# PIC32MZ_cam_sch.net
KiCad netlist of a schematic drawn in Altium Designer
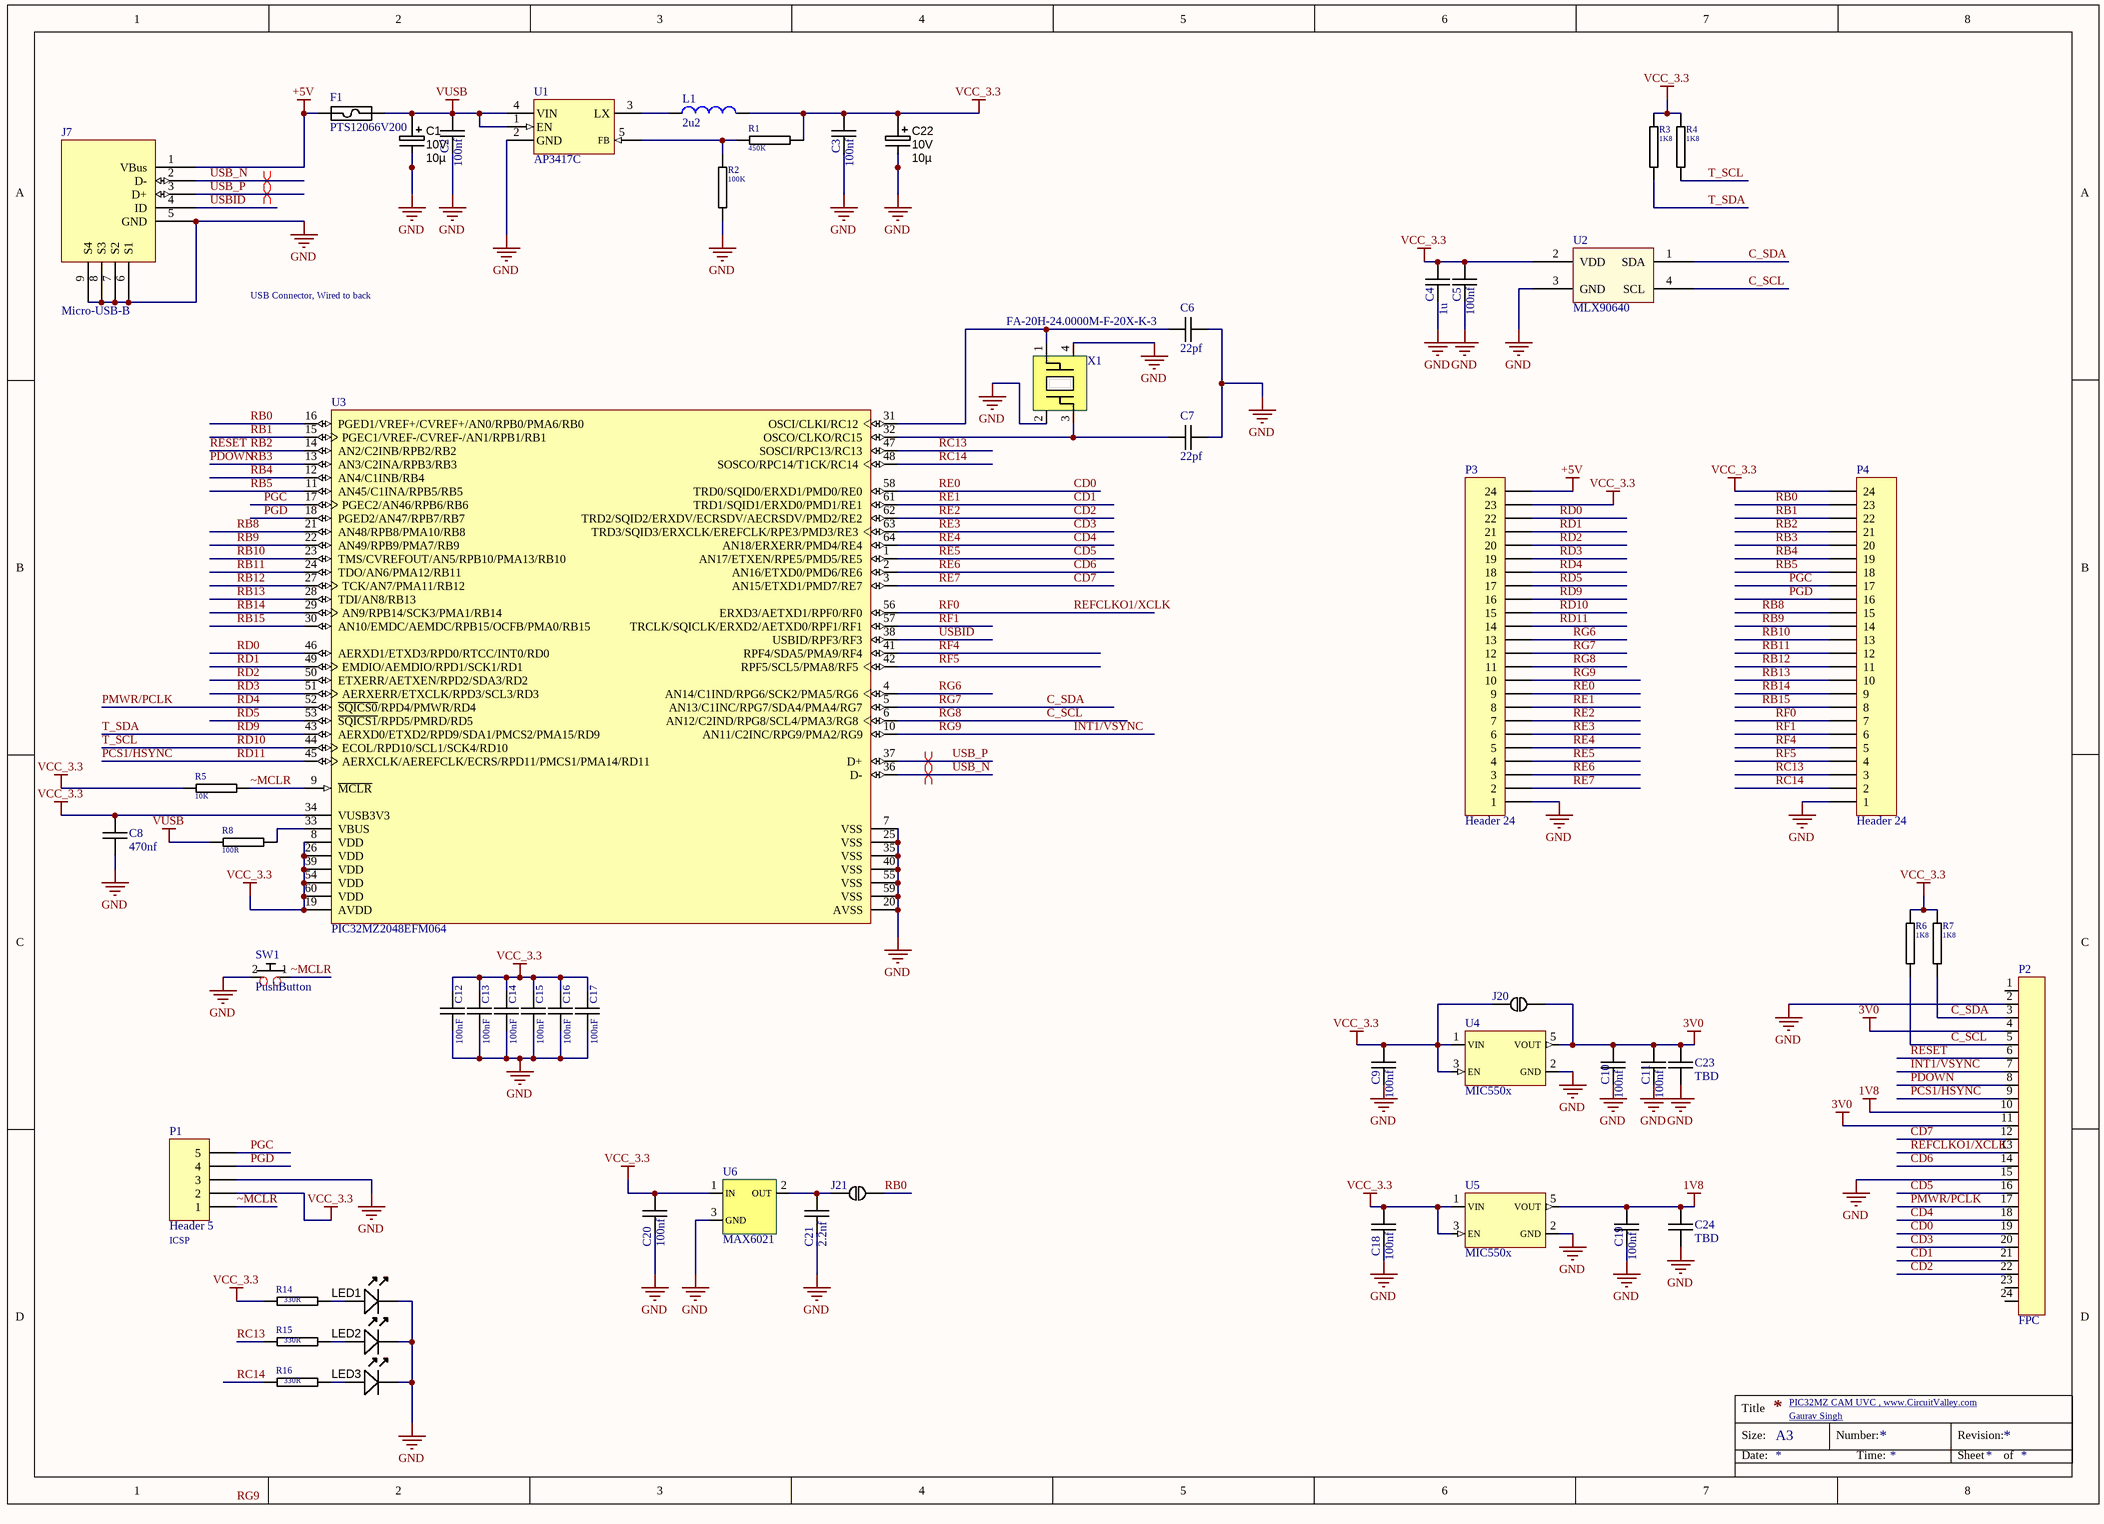
[diagram p0: PIC32MZ_cam_sch.SchDoc]

(export (version "E")
  (design (tool "Eeschema 10.0.6"))
  (components
    (comp (ref "C1")
      (value "10µ")
      (footprint "CAPMP3528X210N")
      (description "Capacitor SMD Tantalum 47uF 20% 6.3V 1210")
      (fields (field (name "TOLERANCE") "±20%") (field (name "RATINGS") "10V"))
      (libsource (lib "PBL - Capacitors") (part "CAPT_47u_1210_6V3"))
    )
    (comp (ref "C2")
      (value "100nf")
      (footprint "0603C-GENERIC")
      (description "CAPACITOR 0603 CERAMIC")
      (fields
        (field (name "MANUFACTURER") "Murata Electronics North America")
        (field (name "MANUFACTURER PART NUMBER") "GRM188R60J106ME47D")
      )
      (libsource (lib "Generic") (part "0603C-10UF-6V3-X5R-MUR"))
    )
    (comp (ref "C3")
      (value "100nf")
      (footprint "0603C-GENERIC")
      (description "CAPACITOR 0603 CERAMIC")
      (fields
        (field (name "MANUFACTURER") "Murata Electronics North America")
        (field (name "MANUFACTURER PART NUMBER") "GRM188R60J106ME47D")
      )
      (libsource (lib "Generic") (part "0603C-10UF-6V3-X5R-MUR"))
    )
    (comp (ref "C4")
      (value "1u")
      (footprint "0603C-GENERIC")
      (description "CAPACITOR 0603 CERAMIC")
      (fields
        (field (name "MANUFACTURER") "Murata Electronics North America")
        (field (name "MANUFACTURER PART NUMBER") "GRM188R60J106ME47D")
      )
      (libsource (lib "Generic") (part "0603C-10UF-6V3-X5R-MUR"))
    )
    (comp (ref "C5")
      (value "100nf")
      (footprint "0603C-GENERIC")
      (description "CAPACITOR 0603 CERAMIC")
      (fields
        (field (name "MANUFACTURER") "Murata Electronics North America")
        (field (name "MANUFACTURER PART NUMBER") "GRM188R60J106ME47D")
      )
      (libsource (lib "Generic") (part "0603C-10UF-6V3-X5R-MUR"))
    )
    (comp (ref "C6")
      (value "22pf")
      (footprint "0603C-GENERIC")
      (description "CAPACITOR 0603 CERAMIC")
      (fields
        (field (name "MANUFACTURER") "Murata Electronics North America")
        (field (name "MANUFACTURER PART NUMBER") "GRM188R60J106ME47D")
      )
      (libsource (lib "Generic") (part "0603C-10UF-6V3-X5R-MUR"))
    )
    (comp (ref "C7")
      (value "22pf")
      (footprint "0603C-GENERIC")
      (description "CAPACITOR 0603 CERAMIC")
      (fields
        (field (name "MANUFACTURER") "Murata Electronics North America")
        (field (name "MANUFACTURER PART NUMBER") "GRM188R60J106ME47D")
      )
      (libsource (lib "Generic") (part "0603C-10UF-6V3-X5R-MUR"))
    )
    (comp (ref "C8")
      (value "470nf")
      (footprint "0603C-GENERIC")
      (description "CAPACITOR 0603 CERAMIC")
      (fields
        (field (name "MANUFACTURER") "Murata Electronics North America")
        (field (name "MANUFACTURER PART NUMBER") "GRM188R60J106ME47D")
      )
      (libsource (lib "Generic") (part "0603C-10UF-6V3-X5R-MUR"))
    )
    (comp (ref "C9")
      (value "100nf")
      (footprint "0603C-GENERIC")
      (description "CAPACITOR 0603 CERAMIC")
      (fields
        (field (name "MANUFACTURER") "Murata Electronics North America")
        (field (name "MANUFACTURER PART NUMBER") "GRM188R60J106ME47D")
      )
      (libsource (lib "Generic") (part "0603C-10UF-6V3-X5R-MUR"))
    )
    (comp (ref "C10")
      (value "100nf")
      (footprint "0603C-GENERIC")
      (description "CAPACITOR 0603 CERAMIC")
      (fields
        (field (name "MANUFACTURER") "Murata Electronics North America")
        (field (name "MANUFACTURER PART NUMBER") "GRM188R60J106ME47D")
      )
      (libsource (lib "Generic") (part "0603C-10UF-6V3-X5R-MUR"))
    )
    (comp (ref "C11")
      (value "100nf")
      (footprint "0603C-GENERIC")
      (description "CAPACITOR 0603 CERAMIC")
      (fields
        (field (name "MANUFACTURER") "Murata Electronics North America")
        (field (name "MANUFACTURER PART NUMBER") "GRM188R60J106ME47D")
      )
      (libsource (lib "Generic") (part "0603C-10UF-6V3-X5R-MUR"))
    )
    (comp (ref "C12")
      (value "100nF")
      (footprint "0603C-GENERIC")
      (description "CAPACITOR 0603 CERAMIC")
      (fields
        (field (name "MANUFACTURER PART NUMBER") "C1608X7R1E104K")
        (field (name "MANUFACTURER") "TDK Corporation")
      )
      (libsource (lib "Generic") (part "0603C-100NF-25V-X7R-TDK"))
    )
    (comp (ref "C13")
      (value "100nF")
      (footprint "0603C-GENERIC")
      (description "CAPACITOR 0603 CERAMIC")
      (fields
        (field (name "MANUFACTURER PART NUMBER") "C1608X7R1E104K")
        (field (name "MANUFACTURER") "TDK Corporation")
      )
      (libsource (lib "Generic") (part "0603C-100NF-25V-X7R-TDK"))
    )
    (comp (ref "C14")
      (value "100nF")
      (footprint "0603C-GENERIC")
      (description "CAPACITOR 0603 CERAMIC")
      (fields
        (field (name "MANUFACTURER PART NUMBER") "C1608X7R1E104K")
        (field (name "MANUFACTURER") "TDK Corporation")
      )
      (libsource (lib "Generic") (part "0603C-100NF-25V-X7R-TDK"))
    )
    (comp (ref "C15")
      (value "100nF")
      (footprint "0603C-GENERIC")
      (description "CAPACITOR 0603 CERAMIC")
      (fields
        (field (name "MANUFACTURER PART NUMBER") "C1608X7R1E104K")
        (field (name "MANUFACTURER") "TDK Corporation")
      )
      (libsource (lib "Generic") (part "0603C-100NF-25V-X7R-TDK"))
    )
    (comp (ref "C16")
      (value "100nF")
      (footprint "0603C-GENERIC")
      (description "CAPACITOR 0603 CERAMIC")
      (fields
        (field (name "MANUFACTURER PART NUMBER") "C1608X7R1E104K")
        (field (name "MANUFACTURER") "TDK Corporation")
      )
      (libsource (lib "Generic") (part "0603C-100NF-25V-X7R-TDK"))
    )
    (comp (ref "C17")
      (value "100nF")
      (footprint "0603C-GENERIC")
      (description "CAPACITOR 0603 CERAMIC")
      (fields
        (field (name "MANUFACTURER PART NUMBER") "C1608X7R1E104K")
        (field (name "MANUFACTURER") "TDK Corporation")
      )
      (libsource (lib "Generic") (part "0603C-100NF-25V-X7R-TDK"))
    )
    (comp (ref "C18")
      (value "100nf")
      (footprint "0603C-GENERIC")
      (description "CAPACITOR 0603 CERAMIC")
      (fields
        (field (name "MANUFACTURER") "Murata Electronics North America")
        (field (name "MANUFACTURER PART NUMBER") "GRM188R60J106ME47D")
      )
      (libsource (lib "Generic") (part "0603C-10UF-6V3-X5R-MUR"))
    )
    (comp (ref "C19")
      (value "100nf")
      (footprint "0603C-GENERIC")
      (description "CAPACITOR 0603 CERAMIC")
      (fields
        (field (name "MANUFACTURER") "Murata Electronics North America")
        (field (name "MANUFACTURER PART NUMBER") "GRM188R60J106ME47D")
      )
      (libsource (lib "Generic") (part "0603C-10UF-6V3-X5R-MUR"))
    )
    (comp (ref "C20")
      (value "100nf")
      (footprint "0603C-GENERIC")
      (description "CAPACITOR 0603 CERAMIC")
      (fields
        (field (name "MANUFACTURER") "Murata Electronics North America")
        (field (name "MANUFACTURER PART NUMBER") "GRM188R60J106ME47D")
      )
      (libsource (lib "Generic") (part "0603C-10UF-6V3-X5R-MUR"))
    )
    (comp (ref "C21")
      (value "2.2nf")
      (footprint "0603C-GENERIC")
      (description "CAPACITOR 0603 CERAMIC")
      (fields
        (field (name "MANUFACTURER") "Murata Electronics North America")
        (field (name "MANUFACTURER PART NUMBER") "GRM188R60J106ME47D")
      )
      (libsource (lib "Generic") (part "0603C-10UF-6V3-X5R-MUR"))
    )
    (comp (ref "C22")
      (value "10µ")
      (footprint "CAPMP3528X210N")
      (description "Capacitor SMD Tantalum 47uF 20% 6.3V 1210")
      (fields (field (name "TOLERANCE") "±20%") (field (name "RATINGS") "10V"))
      (libsource (lib "PBL - Capacitors") (part "CAPT_47u_1210_6V3"))
    )
    (comp (ref "C23")
      (value "TBD")
      (footprint "0805C-TBD")
      (description "CAPACITOR 0805 CERAMIC VALUE TO BE DETERMINED")
      (libsource (lib "Generic") (part "0805C-TBD"))
    )
    (comp (ref "C24")
      (value "TBD")
      (footprint "0805C-TBD")
      (description "CAPACITOR 0805 CERAMIC VALUE TO BE DETERMINED")
      (libsource (lib "Generic") (part "0805C-TBD"))
    )
    (comp (ref "F1")
      (value "PTS12066V200")
      (footprint "RESC3216N")
      (description "GENERIC FUSE")
      (libsource (lib "Generic") (part "FUSE-GENERIC"))
    )
    (comp (ref "J7")
      (value "Micro-USB-B")
      (footprint "10118193-0001lfc")
      (fields (field (name "PART") "10118193-0001lfc"))
      (libsource (lib "USB-MICROB-HW-MC-5F") (part "Micro-USB-B"))
    )
    (comp (ref "J20")
      (value "BYPASS-MINI")
      (footprint "BYPASS-MINI")
      (description "SOLDERDOT BYPASS")
      (libsource (lib "Generic") (part "BYPASS-MINI"))
    )
    (comp (ref "J21")
      (value "BYPASS-MINI")
      (footprint "BYPASS-MINI")
      (description "SOLDERDOT BYPASS")
      (libsource (lib "Generic") (part "BYPASS-MINI"))
    )
    (comp (ref "L1")
      (value "2u2")
      (footprint "TAIYO_NRS4018T2R2MDGJ")
      (fields (field (name "PARTNUMBER") "NRS4018T2R2MDGJ"))
      (libsource (lib "Inductor") (part "inductor_smd"))
    )
    (comp (ref "LED1")
      (value "Blue")
      (footprint "LED-0805-K")
      (description "LED 0805 SMD Blue 100mcd 470nm")
      (libsource (lib "PBL - Light Sources") (part "LED_SMD_Blue_0805_100mcd"))
    )
    (comp (ref "LED2")
      (value "Blue")
      (footprint "LED-0805-K")
      (description "LED 0805 SMD Blue 100mcd 470nm")
      (libsource (lib "PBL - Light Sources") (part "LED_SMD_Blue_0805_100mcd"))
    )
    (comp (ref "LED3")
      (value "Blue")
      (footprint "LED-0805-K")
      (description "LED 0805 SMD Blue 100mcd 470nm")
      (libsource (lib "PBL - Light Sources") (part "LED_SMD_Blue_0805_100mcd"))
    )
    (comp (ref "P1")
      (value "Header 5")
      (footprint "HDR1X5")
      (description "Header, 5-Pin")
      (fields (field (name "PUBLISHER") "Altium Limited"))
      (libsource (lib "Miscellaneous Connectors") (part "Header 5"))
    )
    (comp (ref "P2") (value "FPC") (footprint "OV7xxx Cam") (libsource (lib "cvlib") (part "FPC24_PIN")))
    (comp (ref "P3")
      (value "Header 24")
      (footprint "HDR1X24")
      (description "Header, 24-Pin")
      (fields (field (name "PUBLISHER") "Altium Limited"))
      (libsource (lib "Miscellaneous Connectors") (part "Header 24"))
    )
    (comp (ref "P4")
      (value "Header 24")
      (footprint "HDR1X24")
      (description "Header, 24-Pin")
      (fields (field (name "PUBLISHER") "Altium Limited"))
      (libsource (lib "") (part "Header 24_1"))
    )
    (comp (ref "R1")
      (value "450K")
      (footprint "0603R-10K")
      (description "GENERIC RESISTOR 0603")
      (fields (field (name "MANUFACTURER") "Stackpole Electronics Inc") (field (name "TOLERANCE") "±1%"))
      (libsource (lib "Generic") (part "0603R-10K"))
    )
    (comp (ref "R2")
      (value "100K")
      (footprint "0603R-10K")
      (description "GENERIC RESISTOR 0603")
      (fields (field (name "MANUFACTURER") "Stackpole Electronics Inc") (field (name "TOLERANCE") "±1%"))
      (libsource (lib "Generic") (part "0603R-10K"))
    )
    (comp (ref "R3")
      (value "1K8")
      (footprint "0603R-10K")
      (description "GENERIC RESISTOR 0603")
      (fields (field (name "MANUFACTURER") "Stackpole Electronics Inc") (field (name "TOLERANCE") "±1%"))
      (libsource (lib "Generic") (part "0603R-10K"))
    )
    (comp (ref "R4")
      (value "1K8")
      (footprint "0603R-10K")
      (description "GENERIC RESISTOR 0603")
      (fields (field (name "MANUFACTURER") "Stackpole Electronics Inc") (field (name "TOLERANCE") "±1%"))
      (libsource (lib "Generic") (part "0603R-10K"))
    )
    (comp (ref "R5")
      (value "10K")
      (footprint "0603R-10K")
      (description "GENERIC RESISTOR 0603")
      (fields (field (name "MANUFACTURER") "Stackpole Electronics Inc") (field (name "TOLERANCE") "±1%"))
      (libsource (lib "Generic") (part "0603R-10K"))
    )
    (comp (ref "R6")
      (value "1K8")
      (footprint "0603R-10K")
      (description "GENERIC RESISTOR 0603")
      (fields (field (name "MANUFACTURER") "Stackpole Electronics Inc") (field (name "TOLERANCE") "±1%"))
      (libsource (lib "Generic") (part "0603R-10K"))
    )
    (comp (ref "R7")
      (value "1K8")
      (footprint "0603R-10K")
      (description "GENERIC RESISTOR 0603")
      (fields (field (name "MANUFACTURER") "Stackpole Electronics Inc") (field (name "TOLERANCE") "±1%"))
      (libsource (lib "Generic") (part "0603R-10K"))
    )
    (comp (ref "R8")
      (value "100R")
      (footprint "0603R-10K")
      (description "GENERIC RESISTOR 0603")
      (fields (field (name "MANUFACTURER") "Stackpole Electronics Inc") (field (name "TOLERANCE") "±1%"))
      (libsource (lib "Generic") (part "0603R-10K"))
    )
    (comp (ref "R14")
      (value "330R")
      (footprint "0603R-10K")
      (description "GENERIC RESISTOR 0603")
      (fields (field (name "MANUFACTURER") "Stackpole Electronics Inc") (field (name "TOLERANCE") "±1%"))
      (libsource (lib "Generic") (part "0603R-10K"))
    )
    (comp (ref "R15")
      (value "330R")
      (footprint "0603R-10K")
      (description "GENERIC RESISTOR 0603")
      (fields (field (name "MANUFACTURER") "Stackpole Electronics Inc") (field (name "TOLERANCE") "±1%"))
      (libsource (lib "Generic") (part "0603R-10K"))
    )
    (comp (ref "R16")
      (value "330R")
      (footprint "0603R-10K")
      (description "GENERIC RESISTOR 0603")
      (fields (field (name "MANUFACTURER") "Stackpole Electronics Inc") (field (name "TOLERANCE") "±1%"))
      (libsource (lib "Generic") (part "0603R-10K"))
    )
    (comp (ref "SW1")
      (value "PushButton")
      (footprint "PushButtonGrid5.08x3.81")
      (libsource (lib "PushSwitchSmall") (part "PushButton"))
    )
    (comp (ref "U1") (value "AP3417C") (footprint "SOT23-5") (libsource (lib "cvlib") (part "AP3417C")))
    (comp (ref "U2") (value "MLX90640") (footprint "MLX90640") (libsource (lib "cvlib") (part "MLX90640")))
    (comp (ref "U3")
      (value "PIC32MZ2048EFM064")
      (footprint "MCHP-QFP-PT64_V")
      (libsource (lib "microchip_my") (part "PIC32MZ2048EFM064"))
    )
    (comp (ref "U4") (value "MIC550x") (footprint "SOT23-5") (libsource (lib "cvlib") (part "MIC550x")))
    (comp (ref "U5") (value "MIC550x") (footprint "SOT23-5") (libsource (lib "cvlib") (part "MIC550x")))
    (comp (ref "U6") (value "MAX6021") (footprint "SOT23-3") (libsource (lib "cvlib") (part "MAX6021_Ref")))
    (comp (ref "X1")
      (value "FA-20H-24.0000M-F-20X-K-3")
      (footprint "Active Oscillator 2520")
      (libsource (lib "Crystal_and_oscillator") (part "Crstal_passive_2520"))
    )
  )
  (nets
    (net (code "1") (name "+5V") (class "Default")
      (node (ref "F1") (pin "1") (pintype "passive"))
      (node (ref "J7") (pin "1") (pinfunction "VBus_1") (pintype "power_in"))
      (node (ref "P3") (pin "24") (pinfunction "24_24") (pintype "passive"))
    )
    (net (code "2") (name "/CD0") (class "Default")
      (node (ref "P2") (pin "19") (pinfunction "19_19") (pintype "passive"))
      (node (ref "P3") (pin "9") (pinfunction "9_9") (pintype "passive"))
      (node (ref "U3") (pin "58") (pinfunction "TRD0/SQID0/ERXD1/PMD0/RE0_58") (pintype "bidirectional"))
    )
    (net (code "3") (name "/CD1") (class "Default")
      (node (ref "P2") (pin "21") (pinfunction "21_21") (pintype "passive"))
      (node (ref "P3") (pin "8") (pinfunction "8_8") (pintype "passive"))
      (node (ref "U3") (pin "61") (pinfunction "TRD1/SQID1/ERXD0/PMD1/RE1_61") (pintype "bidirectional"))
    )
    (net (code "4") (name "/CD2") (class "Default")
      (node (ref "P2") (pin "22") (pinfunction "22_22") (pintype "passive"))
      (node (ref "P3") (pin "7") (pinfunction "7_7") (pintype "passive"))
      (node (ref "U3") (pin "62") (pinfunction "TRD2/SQID2/ERXDV/ECRSDV/AECRSDV/PMD2/RE2_62") (pintype "bidirectional"))
    )
    (net (code "5") (name "/CD3") (class "Default")
      (node (ref "P2") (pin "20") (pinfunction "20_20") (pintype "passive"))
      (node (ref "P3") (pin "6") (pinfunction "6_6") (pintype "passive"))
      (node (ref "U3") (pin "63") (pinfunction "TRD3/SQID3/ERXCLK/EREFCLK/RPE3/PMD3/RE3_63") (pintype "bidirectional"))
    )
    (net (code "6") (name "/CD4") (class "Default")
      (node (ref "P2") (pin "18") (pinfunction "18_18") (pintype "passive"))
      (node (ref "P3") (pin "5") (pinfunction "5_5") (pintype "passive"))
      (node (ref "U3") (pin "64") (pinfunction "AN18/ERXERR/PMD4/RE4_64") (pintype "bidirectional"))
    )
    (net (code "7") (name "/CD5") (class "Default")
      (node (ref "P2") (pin "16") (pinfunction "16_16") (pintype "passive"))
      (node (ref "P3") (pin "4") (pinfunction "4_4") (pintype "passive"))
      (node (ref "U3") (pin "1") (pinfunction "AN17/ETXEN/RPE5/PMD5/RE5_1") (pintype "bidirectional"))
    )
    (net (code "8") (name "/CD6") (class "Default")
      (node (ref "P2") (pin "14") (pinfunction "14_14") (pintype "passive"))
      (node (ref "P3") (pin "3") (pinfunction "3_3") (pintype "passive"))
      (node (ref "U3") (pin "2") (pinfunction "AN16/ETXD0/PMD6/RE6_2") (pintype "bidirectional"))
    )
    (net (code "9") (name "/CD7") (class "Default")
      (node (ref "P2") (pin "12") (pinfunction "12_12") (pintype "passive"))
      (node (ref "P3") (pin "2") (pinfunction "2_2") (pintype "passive"))
      (node (ref "U3") (pin "3") (pinfunction "AN15/ETXD1/PMD7/RE7_3") (pintype "bidirectional"))
    )
    (net (code "10") (name "/C_SCL") (class "Default")
      (node (ref "P2") (pin "5") (pinfunction "5_5") (pintype "passive"))
      (node (ref "P3") (pin "11") (pinfunction "11_11") (pintype "passive"))
      (node (ref "R6") (pin "1") (pintype "passive"))
      (node (ref "U2") (pin "4") (pinfunction "SCL_4") (pintype "passive"))
      (node (ref "U3") (pin "6") (pinfunction "AN12/C2IND/RPG8/SCL4/PMA3/RG8_6") (pintype "bidirectional"))
    )
    (net (code "11") (name "/C_SDA") (class "Default")
      (node (ref "P2") (pin "3") (pinfunction "3_3") (pintype "passive"))
      (node (ref "P3") (pin "12") (pinfunction "12_12") (pintype "passive"))
      (node (ref "R7") (pin "1") (pintype "passive"))
      (node (ref "U2") (pin "1") (pinfunction "SDA_1") (pintype "passive"))
      (node (ref "U3") (pin "5") (pinfunction "AN13/C1INC/RPG7/SDA4/PMA4/RG7_5") (pintype "bidirectional"))
    )
    (net (code "12") (name "/INT1{slash}VSYNC") (class "Default")
      (node (ref "P2") (pin "7") (pinfunction "7_7") (pintype "passive"))
      (node (ref "P3") (pin "10") (pinfunction "10_10") (pintype "passive"))
      (node (ref "U3") (pin "10") (pinfunction "AN11/C2INC/RPG9/PMA2/RG9_10") (pintype "bidirectional"))
    )
    (net (code "13") (name "/PCS1{slash}HSYNC") (class "Default")
      (node (ref "P2") (pin "9") (pinfunction "9_9") (pintype "passive"))
      (node (ref "P3") (pin "14") (pinfunction "14_14") (pintype "passive"))
      (node (ref "U3") (pin "45") (pinfunction "AERXCLK/AEREFCLK/ECRS/RPD11/PMCS1/PMA14/RD11_45") (pintype "bidirectional"))
    )
    (net (code "14") (name "/PDOWN") (class "Default")
      (node (ref "P2") (pin "8") (pinfunction "8_8") (pintype "passive"))
      (node (ref "P4") (pin "20") (pinfunction "20_20") (pintype "passive"))
      (node (ref "U3") (pin "13") (pinfunction "AN3/C2INA/RPB3/RB3_13") (pintype "bidirectional"))
    )
    (net (code "15") (name "/PGC") (class "Default")
      (node (ref "P1") (pin "5") (pinfunction "5_5") (pintype "passive"))
      (node (ref "P4") (pin "17") (pinfunction "17_17") (pintype "passive"))
      (node (ref "U3") (pin "17") (pinfunction "PGEC2/AN46/RPB6/RB6_17") (pintype "bidirectional"))
    )
    (net (code "16") (name "/PGD") (class "Default")
      (node (ref "P1") (pin "4") (pinfunction "4_4") (pintype "passive"))
      (node (ref "P4") (pin "16") (pinfunction "16_16") (pintype "passive"))
      (node (ref "U3") (pin "18") (pinfunction "PGED2/AN47/RPB7/RB7_18") (pintype "bidirectional"))
    )
    (net (code "17") (name "/PMWR{slash}PCLK") (class "Default")
      (node (ref "P2") (pin "17") (pinfunction "17_17") (pintype "passive"))
      (node (ref "P3") (pin "18") (pinfunction "18_18") (pintype "passive"))
      (node (ref "U3") (pin "52") (pinfunction "~{SQICS0}/RPD4/PMWR/RD4_52") (pintype "bidirectional"))
    )
    (net (code "18") (name "/RB0") (class "Default")
      (node (ref "J21") (pin "1") (pinfunction "1_1") (pintype "passive"))
      (node (ref "P4") (pin "23") (pinfunction "23_23") (pintype "passive"))
      (node (ref "U3") (pin "16") (pinfunction "PGED1/VREF+/CVREF+/AN0/RPB0/PMA6/RB0_16") (pintype "bidirectional"))
    )
    (net (code "19") (name "/RB1") (class "Default")
      (node (ref "P4") (pin "22") (pinfunction "22_22") (pintype "passive"))
      (node (ref "U3") (pin "15") (pinfunction "PGEC1/VREF-/CVREF-/AN1/RPB1/RB1_15") (pintype "bidirectional"))
    )
    (net (code "20") (name "/RB2") (class "Default")
      (node (ref "P2") (pin "6") (pinfunction "6_6") (pintype "passive"))
      (node (ref "P4") (pin "21") (pinfunction "21_21") (pintype "passive"))
      (node (ref "U3") (pin "14") (pinfunction "AN2/C2INB/RPB2/RB2_14") (pintype "bidirectional"))
    )
    (net (code "21") (name "/RB4") (class "Default")
      (node (ref "P4") (pin "19") (pinfunction "19_19") (pintype "passive"))
      (node (ref "U3") (pin "12") (pinfunction "AN4/C1INB/RB4_12") (pintype "bidirectional"))
    )
    (net (code "22") (name "/RB5") (class "Default")
      (node (ref "P4") (pin "18") (pinfunction "18_18") (pintype "passive"))
      (node (ref "U3") (pin "11") (pinfunction "AN45/C1INA/RPB5/RB5_11") (pintype "bidirectional"))
    )
    (net (code "23") (name "/RB8") (class "Default")
      (node (ref "P4") (pin "15") (pinfunction "15_15") (pintype "passive"))
      (node (ref "U3") (pin "21") (pinfunction "AN48/RPB8/PMA10/RB8_21") (pintype "bidirectional"))
    )
    (net (code "24") (name "/RB9") (class "Default")
      (node (ref "P4") (pin "14") (pinfunction "14_14") (pintype "passive"))
      (node (ref "U3") (pin "22") (pinfunction "AN49/RPB9/PMA7/RB9_22") (pintype "bidirectional"))
    )
    (net (code "25") (name "/RB10") (class "Default")
      (node (ref "P4") (pin "13") (pinfunction "13_13") (pintype "passive"))
      (node (ref "U3") (pin "23") (pinfunction "TMS/CVREFOUT/AN5/RPB10/PMA13/RB10_23") (pintype "bidirectional"))
    )
    (net (code "26") (name "/RB11") (class "Default")
      (node (ref "P4") (pin "12") (pinfunction "12_12") (pintype "passive"))
      (node (ref "U3") (pin "24") (pinfunction "TDO/AN6/PMA12/RB11_24") (pintype "bidirectional"))
    )
    (net (code "27") (name "/RB12") (class "Default")
      (node (ref "P4") (pin "11") (pinfunction "11_11") (pintype "passive"))
      (node (ref "U3") (pin "27") (pinfunction "TCK/AN7/PMA11/RB12_27") (pintype "bidirectional"))
    )
    (net (code "28") (name "/RB13") (class "Default")
      (node (ref "P4") (pin "10") (pinfunction "10_10") (pintype "passive"))
      (node (ref "U3") (pin "28") (pinfunction "TDI/AN8/RB13_28") (pintype "bidirectional"))
    )
    (net (code "29") (name "/RB14") (class "Default")
      (node (ref "P4") (pin "9") (pinfunction "9_9") (pintype "passive"))
      (node (ref "U3") (pin "29") (pinfunction "AN9/RPB14/SCK3/PMA1/RB14_29") (pintype "bidirectional"))
    )
    (net (code "30") (name "/RB15") (class "Default")
      (node (ref "P4") (pin "8") (pinfunction "8_8") (pintype "passive"))
      (node (ref "U3") (pin "30") (pinfunction "AN10/EMDC/AEMDC/RPB15/OCFB/PMA0/RB15_30") (pintype "bidirectional"))
    )
    (net (code "31") (name "/RC13") (class "Default")
      (node (ref "P4") (pin "3") (pinfunction "3_3") (pintype "passive"))
      (node (ref "R15") (pin "1") (pintype "passive"))
      (node (ref "U3") (pin "47") (pinfunction "SOSCI/RPC13/RC13_47") (pintype "bidirectional"))
    )
    (net (code "32") (name "/RC14") (class "Default")
      (node (ref "P4") (pin "2") (pinfunction "2_2") (pintype "passive"))
      (node (ref "R16") (pin "1") (pintype "passive"))
      (node (ref "U3") (pin "48") (pinfunction "SOSCO/RPC14/T1CK/RC14_48") (pintype "bidirectional"))
    )
    (net (code "33") (name "/RD0") (class "Default")
      (node (ref "P3") (pin "22") (pinfunction "22_22") (pintype "passive"))
      (node (ref "U3") (pin "46") (pinfunction "AERXD1/ETXD3/RPD0/RTCC/INT0/RD0_46") (pintype "bidirectional"))
    )
    (net (code "34") (name "/RD1") (class "Default")
      (node (ref "P3") (pin "21") (pinfunction "21_21") (pintype "passive"))
      (node (ref "U3") (pin "49") (pinfunction "EMDIO/AEMDIO/RPD1/SCK1/RD1_49") (pintype "bidirectional"))
    )
    (net (code "35") (name "/RD2") (class "Default")
      (node (ref "P3") (pin "20") (pinfunction "20_20") (pintype "passive"))
      (node (ref "U3") (pin "50") (pinfunction "ETXERR/AETXEN/RPD2/SDA3/RD2_50") (pintype "bidirectional"))
    )
    (net (code "36") (name "/RD3") (class "Default")
      (node (ref "P3") (pin "19") (pinfunction "19_19") (pintype "passive"))
      (node (ref "U3") (pin "51") (pinfunction "AERXERR/ETXCLK/RPD3/SCL3/RD3_51") (pintype "bidirectional"))
    )
    (net (code "37") (name "/RD5") (class "Default")
      (node (ref "P3") (pin "17") (pinfunction "17_17") (pintype "passive"))
      (node (ref "U3") (pin "53") (pinfunction "~{SQICS1}/RPD5/PMRD/RD5_53") (pintype "bidirectional"))
    )
    (net (code "38") (name "/RD9") (class "Default")
      (node (ref "P3") (pin "16") (pinfunction "16_16") (pintype "passive"))
      (node (ref "R3") (pin "1") (pintype "passive"))
      (node (ref "U3") (pin "43") (pinfunction "AERXD0/ETXD2/RPD9/SDA1/PMCS2/PMA15/RD9_43") (pintype "bidirectional"))
    )
    (net (code "39") (name "/RD10") (class "Default")
      (node (ref "P3") (pin "15") (pinfunction "15_15") (pintype "passive"))
      (node (ref "R4") (pin "1") (pintype "passive"))
      (node (ref "U3") (pin "44") (pinfunction "ECOL/RPD10/SCL1/SCK4/RD10_44") (pintype "bidirectional"))
    )
    (net (code "40") (name "/REFCLKO1{slash}XCLK") (class "Default")
      (node (ref "P2") (pin "13") (pinfunction "13_13") (pintype "passive"))
      (node (ref "P4") (pin "7") (pinfunction "7_7") (pintype "passive"))
      (node (ref "U3") (pin "56") (pinfunction "ERXD3/AETXD1/RPF0/RF0_56") (pintype "bidirectional"))
    )
    (net (code "41") (name "/RF1") (class "Default")
      (node (ref "P4") (pin "6") (pinfunction "6_6") (pintype "passive"))
      (node (ref "U3") (pin "57") (pinfunction "TRCLK/SQICLK/ERXD2/AETXD0/RPF1/RF1_57") (pintype "bidirectional"))
    )
    (net (code "42") (name "/RF4") (class "Default")
      (node (ref "P4") (pin "5") (pinfunction "5_5") (pintype "passive"))
      (node (ref "U3") (pin "41") (pinfunction "RPF4/SDA5/PMA9/RF4_41") (pintype "bidirectional"))
    )
    (net (code "43") (name "/RF5") (class "Default")
      (node (ref "P4") (pin "4") (pinfunction "4_4") (pintype "passive"))
      (node (ref "U3") (pin "42") (pinfunction "RPF5/SCL5/PMA8/RF5_42") (pintype "bidirectional"))
    )
    (net (code "44") (name "/RG6") (class "Default")
      (node (ref "P3") (pin "13") (pinfunction "13_13") (pintype "passive"))
      (node (ref "U3") (pin "4") (pinfunction "AN14/C1IND/RPG6/SCK2/PMA5/RG6_4") (pintype "bidirectional"))
    )
    (net (code "45") (name "/USBID") (class "Default")
      (node (ref "J7") (pin "4") (pinfunction "ID_4") (pintype "passive"))
      (node (ref "U3") (pin "38") (pinfunction "USBID/RPF3/RF3_38") (pintype "bidirectional"))
    )
    (net (code "46") (name "/USB_N") (class "Default")
      (node (ref "J7") (pin "2") (pinfunction "D-_2") (pintype "bidirectional"))
      (node (ref "U3") (pin "36") (pinfunction "D-_36") (pintype "bidirectional"))
    )
    (net (code "47") (name "/USB_P") (class "Default")
      (node (ref "J7") (pin "3") (pinfunction "D+_3") (pintype "bidirectional"))
      (node (ref "U3") (pin "37") (pinfunction "D+_37") (pintype "bidirectional"))
    )
    (net (code "48") (name "/~MCLR") (class "Default")
      (node (ref "P1") (pin "1") (pinfunction "1_1") (pintype "passive"))
      (node (ref "R5") (pin "2") (pintype "passive"))
      (node (ref "SW1") (pin "1") (pinfunction "P1_1") (pintype "passive"))
      (node (ref "U3") (pin "9") (pinfunction "~{MCLR}_9") (pintype "input"))
    )
    (net (code "49") (name "1V8") (class "Default")
      (node (ref "C19") (pin "2") (pintype "passive"))
      (node (ref "C24") (pin "1") (pintype "passive"))
      (node (ref "P2") (pin "10") (pinfunction "10_10") (pintype "passive"))
      (node (ref "U5") (pin "5") (pinfunction "VOUT_5") (pintype "output"))
    )
    (net (code "50") (name "3V0") (class "Default")
      (node (ref "C10") (pin "2") (pintype "passive"))
      (node (ref "C11") (pin "2") (pintype "passive"))
      (node (ref "C23") (pin "1") (pintype "passive"))
      (node (ref "J20") (pin "1") (pinfunction "1_1") (pintype "passive"))
      (node (ref "P2") (pin "11") (pinfunction "11_11") (pintype "passive"))
      (node (ref "P2") (pin "4") (pinfunction "4_4") (pintype "passive"))
      (node (ref "U4") (pin "5") (pinfunction "VOUT_5") (pintype "output"))
    )
    (net (code "51") (name "GND") (class "Default")
      (node (ref "C1") (pin "2") (pintype "passive"))
      (node (ref "C10") (pin "1") (pintype "passive"))
      (node (ref "C11") (pin "1") (pintype "passive"))
      (node (ref "C12") (pin "1") (pintype "passive"))
      (node (ref "C13") (pin "1") (pintype "passive"))
      (node (ref "C14") (pin "1") (pintype "passive"))
      (node (ref "C15") (pin "1") (pintype "passive"))
      (node (ref "C16") (pin "1") (pintype "passive"))
      (node (ref "C17") (pin "1") (pintype "passive"))
      (node (ref "C18") (pin "1") (pintype "passive"))
      (node (ref "C19") (pin "1") (pintype "passive"))
      (node (ref "C2") (pin "1") (pintype "passive"))
      (node (ref "C20") (pin "1") (pintype "passive"))
      (node (ref "C21") (pin "1") (pintype "passive"))
      (node (ref "C22") (pin "2") (pintype "passive"))
      (node (ref "C23") (pin "2") (pintype "passive"))
      (node (ref "C24") (pin "2") (pintype "passive"))
      (node (ref "C3") (pin "1") (pintype "passive"))
      (node (ref "C4") (pin "1") (pintype "passive"))
      (node (ref "C5") (pin "1") (pintype "passive"))
      (node (ref "C6") (pin "1") (pintype "passive"))
      (node (ref "C7") (pin "1") (pintype "passive"))
      (node (ref "C8") (pin "2") (pintype "passive"))
      (node (ref "C9") (pin "1") (pintype "passive"))
      (node (ref "J7") (pin "5") (pinfunction "GND_5") (pintype "power_in"))
      (node (ref "J7") (pin "6") (pinfunction "S1_6") (pintype "passive"))
      (node (ref "J7") (pin "7") (pinfunction "S2_7") (pintype "power_in"))
      (node (ref "J7") (pin "8") (pinfunction "S3_8") (pintype "power_in"))
      (node (ref "J7") (pin "9") (pinfunction "S4_9") (pintype "power_in"))
      (node (ref "LED1") (pin "K") (pinfunction "K_K") (pintype "passive"))
      (node (ref "LED2") (pin "K") (pinfunction "K_K") (pintype "passive"))
      (node (ref "LED3") (pin "K") (pinfunction "K_K") (pintype "passive"))
      (node (ref "P1") (pin "3") (pinfunction "3_3") (pintype "passive"))
      (node (ref "P2") (pin "15") (pinfunction "15_15") (pintype "passive"))
      (node (ref "P2") (pin "2") (pinfunction "2_2") (pintype "passive"))
      (node (ref "P3") (pin "1") (pinfunction "1_1") (pintype "passive"))
      (node (ref "P4") (pin "1") (pinfunction "1_1") (pintype "passive"))
      (node (ref "R2") (pin "1") (pintype "passive"))
      (node (ref "SW1") (pin "2") (pinfunction "P2_2") (pintype "passive"))
      (node (ref "U1") (pin "2") (pinfunction "GND_2") (pintype "power_in"))
      (node (ref "U2") (pin "3") (pinfunction "GND_3") (pintype "passive"))
      (node (ref "U3") (pin "20") (pinfunction "AVSS_20") (pintype "power_in"))
      (node (ref "U3") (pin "25") (pinfunction "VSS_25") (pintype "power_in"))
      (node (ref "U3") (pin "35") (pinfunction "VSS_35") (pintype "power_in"))
      (node (ref "U3") (pin "40") (pinfunction "VSS_40") (pintype "power_in"))
      (node (ref "U3") (pin "55") (pinfunction "VSS_55") (pintype "power_in"))
      (node (ref "U3") (pin "59") (pinfunction "VSS_59") (pintype "power_in"))
      (node (ref "U3") (pin "7") (pinfunction "VSS_7") (pintype "power_in"))
      (node (ref "U4") (pin "2") (pinfunction "GND_2") (pintype "power_in"))
      (node (ref "U5") (pin "2") (pinfunction "GND_2") (pintype "power_in"))
      (node (ref "U6") (pin "3") (pinfunction "GND_3") (pintype "power_in"))
      (node (ref "X1") (pin "2") (pinfunction "2_2") (pintype "passive"))
      (node (ref "X1") (pin "4") (pinfunction "4_4") (pintype "passive"))
    )
    (net (code "52") (name "Net-(LED1-PadA)") (class "Default")
      (node (ref "LED1") (pin "A") (pinfunction "A_A") (pintype "passive"))
      (node (ref "R14") (pin "2") (pintype "passive"))
    )
    (net (code "53") (name "Net-(LED2-PadA)") (class "Default")
      (node (ref "LED2") (pin "A") (pinfunction "A_A") (pintype "passive"))
      (node (ref "R15") (pin "2") (pintype "passive"))
    )
    (net (code "54") (name "Net-(LED3-PadA)") (class "Default")
      (node (ref "LED3") (pin "A") (pinfunction "A_A") (pintype "passive"))
      (node (ref "R16") (pin "2") (pintype "passive"))
    )
    (net (code "55") (name "Net-(U1-FB)") (class "Default")
      (node (ref "R1") (pin "1") (pintype "passive"))
      (node (ref "R2") (pin "2") (pintype "passive"))
      (node (ref "U1") (pin "5") (pinfunction "FB_5") (pintype "input"))
    )
    (net (code "56") (name "Net-(U1-LX)") (class "Default")
      (node (ref "L1") (pin "1") (pinfunction "1_1") (pintype "passive"))
      (node (ref "U1") (pin "3") (pinfunction "LX_3") (pintype "passive"))
    )
    (net (code "57") (name "Net-(U3-OSCI{slash}CLKI{slash}RC12)") (class "Default")
      (node (ref "C6") (pin "2") (pintype "passive"))
      (node (ref "U3") (pin "31") (pinfunction "OSCI/CLKI/RC12_31") (pintype "bidirectional"))
      (node (ref "X1") (pin "1") (pinfunction "1_1") (pintype "passive"))
    )
    (net (code "58") (name "Net-(U3-OSCO{slash}CLKO{slash}RC15)") (class "Default")
      (node (ref "C7") (pin "2") (pintype "passive"))
      (node (ref "U3") (pin "32") (pinfunction "OSCO/CLKO/RC15_32") (pintype "bidirectional"))
      (node (ref "X1") (pin "3") (pinfunction "3_3") (pintype "passive"))
    )
    (net (code "59") (name "Net-(U3-VBUS)") (class "Default")
      (node (ref "R8") (pin "2") (pintype "passive"))
      (node (ref "U3") (pin "33") (pinfunction "VBUS_33") (pintype "power_in"))
    )
    (net (code "60") (name "Net-(U6-OUT)") (class "Default")
      (node (ref "C21") (pin "2") (pintype "passive"))
      (node (ref "J21") (pin "2") (pinfunction "2_2") (pintype "passive"))
      (node (ref "U6") (pin "2") (pinfunction "OUT_2") (pintype "power_in"))
    )
    (net (code "61") (name "VCC_3.3") (class "Default")
      (node (ref "C12") (pin "2") (pintype "passive"))
      (node (ref "C13") (pin "2") (pintype "passive"))
      (node (ref "C14") (pin "2") (pintype "passive"))
      (node (ref "C15") (pin "2") (pintype "passive"))
      (node (ref "C16") (pin "2") (pintype "passive"))
      (node (ref "C17") (pin "2") (pintype "passive"))
      (node (ref "C18") (pin "2") (pintype "passive"))
      (node (ref "C20") (pin "2") (pintype "passive"))
      (node (ref "C22") (pin "1") (pintype "passive"))
      (node (ref "C3") (pin "2") (pintype "passive"))
      (node (ref "C4") (pin "2") (pintype "passive"))
      (node (ref "C5") (pin "2") (pintype "passive"))
      (node (ref "C8") (pin "1") (pintype "passive"))
      (node (ref "C9") (pin "2") (pintype "passive"))
      (node (ref "J20") (pin "2") (pinfunction "2_2") (pintype "passive"))
      (node (ref "L1") (pin "2") (pinfunction "2_2") (pintype "passive"))
      (node (ref "P1") (pin "2") (pinfunction "2_2") (pintype "passive"))
      (node (ref "P3") (pin "23") (pinfunction "23_23") (pintype "passive"))
      (node (ref "P4") (pin "24") (pinfunction "24_24") (pintype "passive"))
      (node (ref "R1") (pin "2") (pintype "passive"))
      (node (ref "R14") (pin "1") (pintype "passive"))
      (node (ref "R3") (pin "2") (pintype "passive"))
      (node (ref "R4") (pin "2") (pintype "passive"))
      (node (ref "R5") (pin "1") (pintype "passive"))
      (node (ref "R6") (pin "2") (pintype "passive"))
      (node (ref "R7") (pin "2") (pintype "passive"))
      (node (ref "U2") (pin "2") (pinfunction "VDD_2") (pintype "passive"))
      (node (ref "U3") (pin "19") (pinfunction "AVDD_19") (pintype "power_in"))
      (node (ref "U3") (pin "26") (pinfunction "VDD_26") (pintype "power_in"))
      (node (ref "U3") (pin "34") (pinfunction "VUSB3V3_34") (pintype "power_in"))
      (node (ref "U3") (pin "39") (pinfunction "VDD_39") (pintype "power_in"))
      (node (ref "U3") (pin "54") (pinfunction "VDD_54") (pintype "power_in"))
      (node (ref "U3") (pin "60") (pinfunction "VDD_60") (pintype "power_in"))
      (node (ref "U3") (pin "8") (pinfunction "VDD_8") (pintype "power_in"))
      (node (ref "U4") (pin "1") (pinfunction "VIN_1") (pintype "power_in"))
      (node (ref "U4") (pin "3") (pinfunction "EN_3") (pintype "input"))
      (node (ref "U5") (pin "1") (pinfunction "VIN_1") (pintype "power_in"))
      (node (ref "U5") (pin "3") (pinfunction "EN_3") (pintype "input"))
      (node (ref "U6") (pin "1") (pinfunction "IN_1") (pintype "power_in"))
    )
    (net (code "62") (name "VUSB") (class "Default")
      (node (ref "C1") (pin "1") (pintype "passive"))
      (node (ref "C2") (pin "2") (pintype "passive"))
      (node (ref "F1") (pin "2") (pintype "passive"))
      (node (ref "R8") (pin "1") (pintype "passive"))
      (node (ref "U1") (pin "1") (pinfunction "EN_1") (pintype "input"))
      (node (ref "U1") (pin "4") (pinfunction "VIN_4") (pintype "power_in"))
    )
    (net (code "63") (name "unconnected-(P2-Pad1)") (class "Default")
      (node (ref "P2") (pin "1") (pinfunction "1_1") (pintype "passive"))
    )
    (net (code "64") (name "unconnected-(P2-Pad23)") (class "Default")
      (node (ref "P2") (pin "23") (pinfunction "23_23") (pintype "passive"))
    )
    (net (code "65") (name "unconnected-(P2-Pad24)") (class "Default")
      (node (ref "P2") (pin "24") (pinfunction "24_24") (pintype "passive"))
    )
  )
)
